# 08-Power.net
KiCad netlist of a schematic drawn in Altium Designer
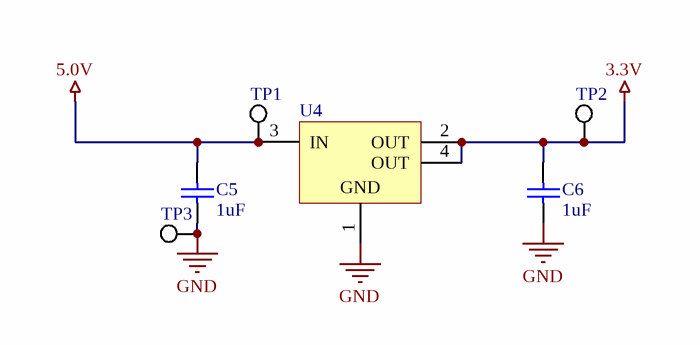
[diagram p0: 08-Power.SchDoc]

(export (version "E")
  (design (tool "Eeschema 10.0.6"))
  (components
    (comp (ref "C5")
      (value "C1206C105K3RACTU")
      (footprint "CAPC3216X180X50ML20T25")
      (description "Chip Capacitor, 1 uF, +/- 10%, 25 V, -55 to 125 degC, 1206 (3216 Metric), RoHS, Tape and Reel")
      (fields
        (field (name "CAPACITANCE") "1uF")
        (field (name "MANUFACTURER") "Kemet")
        (field (name "TOLERANCE") "10%")
      )
      (libsource (lib "Altium Content Vault") (part "CAP-NP-2"))
    )
    (comp (ref "C6")
      (value "C1206C105K3RACTU")
      (footprint "CAPC3216X180X50ML20T25")
      (description "Chip Capacitor, 1 uF, +/- 10%, 25 V, -55 to 125 degC, 1206 (3216 Metric), RoHS, Tape and Reel")
      (fields
        (field (name "CAPACITANCE") "1uF")
        (field (name "MANUFACTURER") "Kemet")
        (field (name "TOLERANCE") "10%")
      )
      (libsource (lib "Altium Content Vault") (part "CAP-NP-2"))
    )
    (comp (ref "TP1")
      (value "5019")
      (footprint "KSTN-5019_V")
      (description "Test Point, 1 Position SMD, RoHS, Tape and Reel")
      (libsource (lib "Altium Content Vault") (part "TESTPOINT_WHITE"))
    )
    (comp (ref "TP2")
      (value "5019")
      (footprint "KSTN-5019_V")
      (description "Test Point, 1 Position SMD, RoHS, Tape and Reel")
      (libsource (lib "Altium Content Vault") (part "TESTPOINT_WHITE"))
    )
    (comp (ref "TP3")
      (value "5019")
      (footprint "KSTN-5019_V")
      (description "Test Point, 1 Position SMD, RoHS, Tape and Reel")
      (libsource (lib "Altium Content Vault") (part "TESTPOINT_WHITE"))
    )
    (comp (ref "U4")
      (value "TLV1117LV33DCYR")
      (footprint "DCY0004A_N")
      (fields (field (name "MANUFACTURER") "Texas Instruments"))
      (libsource (lib "Altium Content Vault") (part "TI-TLV1117LV33DCY4"))
    )
  )
  (nets
    (net (code "1") (name "3.3V") (class "Default")
      (node (ref "C6") (pin "2") (pinfunction "2_2") (pintype "passive"))
      (node (ref "TP2") (pin "1") (pinfunction "1_1") (pintype "passive"))
      (node (ref "U4") (pin "2") (pinfunction "OUT_2") (pintype "power_in"))
      (node (ref "U4") (pin "4") (pinfunction "OUT_4") (pintype "power_in"))
    )
    (net (code "2") (name "5.0V") (class "Default")
      (node (ref "C5") (pin "2") (pinfunction "2_2") (pintype "passive"))
      (node (ref "TP1") (pin "1") (pinfunction "1_1") (pintype "passive"))
      (node (ref "U4") (pin "3") (pinfunction "IN_3") (pintype "power_in"))
    )
    (net (code "3") (name "GND") (class "Default")
      (node (ref "C5") (pin "1") (pinfunction "1_1") (pintype "passive"))
      (node (ref "C6") (pin "1") (pinfunction "1_1") (pintype "passive"))
      (node (ref "TP3") (pin "1") (pinfunction "1_1") (pintype "passive"))
      (node (ref "U4") (pin "1") (pinfunction "GND_1") (pintype "power_in"))
    )
  )
)
